# insider.net
KiCad netlist of a schematic drawn in EAGLE
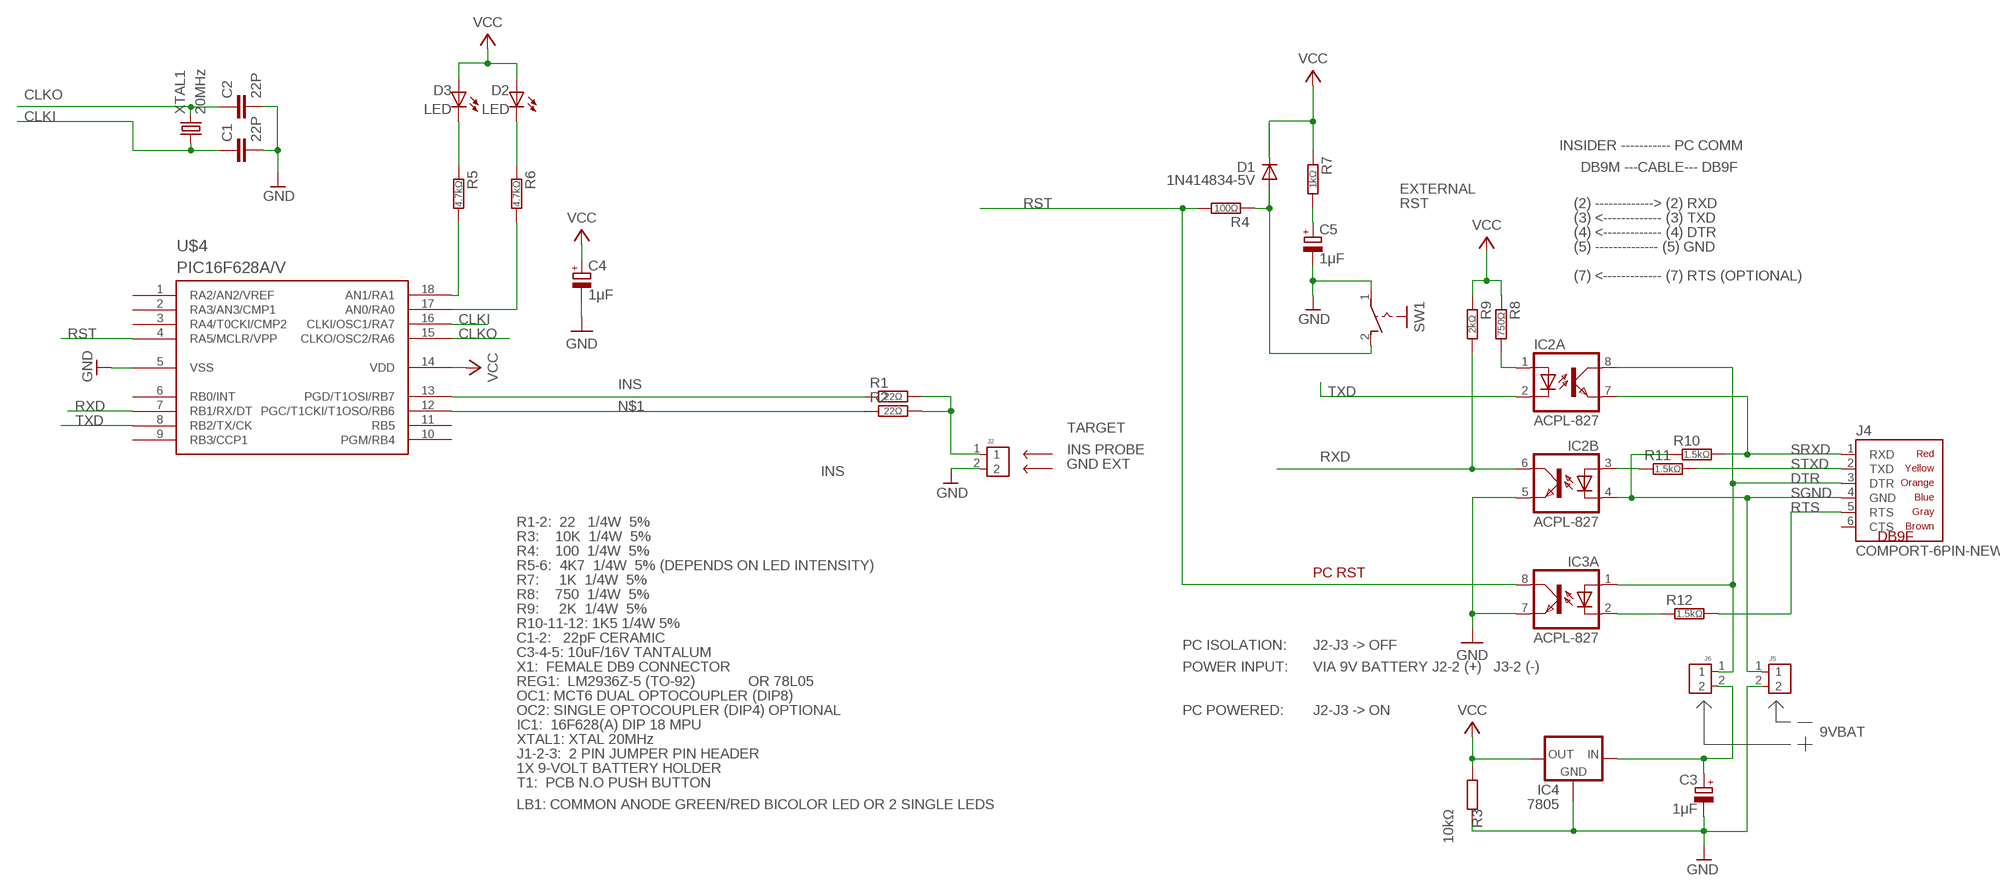
[diagram p0: schematic, sheet 1]

(export (version "E")
  (design (tool "Eeschema 10.0.6"))
  (components
    (comp (ref "C1")
      (value "22P")
      (footprint "eagle-import:C025-020X036")
      (libsource (lib "eagle-import") (part "C025-020X036"))
    )
    (comp (ref "C2")
      (value "22P")
      (footprint "eagle-import:C025-020X036")
      (libsource (lib "eagle-import") (part "C025-020X036"))
    )
    (comp (ref "C3")
      (value "1μF")
      (footprint "eagle-import:E2.5-4_V")
      (libsource (lib "eagle-import") (part "CPOLE2,5-4/V"))
    )
    (comp (ref "C4")
      (value "1μF")
      (footprint "eagle-import:E2.5-4_V")
      (libsource (lib "eagle-import") (part "CPOLE2,5-4/V"))
    )
    (comp (ref "C5")
      (value "1μF")
      (footprint "eagle-import:E2.5-4_V")
      (libsource (lib "eagle-import") (part "CPOLE2,5-4/V"))
    )
    (comp (ref "D1")
      (value "1N414834-5V")
      (footprint "eagle-import:DO34-5V")
      (libsource (lib "eagle-import") (part "1N414834-5V"))
    )
    (comp (ref "D2")
      (value "LED")
      (footprint "eagle-import:LED3MM")
      (libsource (lib "eagle-import") (part "LED"))
    )
    (comp (ref "D3")
      (value "LED")
      (footprint "eagle-import:LED3MM")
      (libsource (lib "eagle-import") (part "LED"))
    )
    (comp (ref "IC2")
      (value "ACPL-827")
      (footprint "eagle-import:DIL08")
      (libsource (lib "eagle-import") (part "ACPL-827"))
    )
    (comp (ref "IC3")
      (value "ACPL-827")
      (footprint "eagle-import:DIL08")
      (libsource (lib "eagle-import") (part "ACPL-827"))
    )
    (comp (ref "IC4")
      (value "7805")
      (footprint "eagle-import:TO220")
      (libsource (lib "eagle-import") (part "LM78"))
    )
    (comp (ref "J2")
      (value "CONN-2P2P/V")
      (footprint "eagle-import:CONN-2P-V")
      (libsource (lib "eagle-import") (part "CONN-2P2P/V"))
    )
    (comp (ref "J4")
      (value "COMPORT-6PIN-NEW")
      (footprint "eagle-import:RS232-6PIN-NEW")
      (libsource (lib "eagle-import") (part "COMPORT-6PIN-NEW"))
    )
    (comp (ref "J5")
      (value "CONN-2P2P/V")
      (footprint "eagle-import:CONN-2P-V")
      (libsource (lib "eagle-import") (part "CONN-2P2P/V"))
    )
    (comp (ref "J6")
      (value "CONN-2P2P/V")
      (footprint "eagle-import:CONN-2P-V")
      (libsource (lib "eagle-import") (part "CONN-2P2P/V"))
    )
    (comp (ref "R1")
      (value "22Ω")
      (footprint "eagle-import:0204_10")
      (libsource (lib "eagle-import") (part "R0204/10"))
    )
    (comp (ref "R2")
      (value "22Ω")
      (footprint "eagle-import:0204_10")
      (libsource (lib "eagle-import") (part "R0204/10"))
    )
    (comp (ref "R3")
      (value "10kΩ")
      (footprint "eagle-import:0204_10")
      (libsource (lib "eagle-import") (part "R0204/10"))
    )
    (comp (ref "R4")
      (value "100Ω")
      (footprint "eagle-import:0204_15")
      (libsource (lib "eagle-import") (part "R0204/15"))
    )
    (comp (ref "R5")
      (value "4.7kΩ")
      (footprint "eagle-import:0204_10")
      (libsource (lib "eagle-import") (part "R0204/10"))
    )
    (comp (ref "R6")
      (value "4.7kΩ")
      (footprint "eagle-import:0204_10")
      (libsource (lib "eagle-import") (part "R0204/10"))
    )
    (comp (ref "R7")
      (value "1kΩ")
      (footprint "eagle-import:0204_10")
      (libsource (lib "eagle-import") (part "R0204/10"))
    )
    (comp (ref "R8")
      (value "750Ω")
      (footprint "eagle-import:0204_12")
      (libsource (lib "eagle-import") (part "R0204/12"))
    )
    (comp (ref "R9")
      (value "2kΩ")
      (footprint "eagle-import:0204_12")
      (libsource (lib "eagle-import") (part "R0204/12"))
    )
    (comp (ref "R10")
      (value "1.5kΩ")
      (footprint "eagle-import:0204_10")
      (libsource (lib "eagle-import") (part "R0204/10"))
    )
    (comp (ref "R11")
      (value "1.5kΩ")
      (footprint "eagle-import:0204_10")
      (libsource (lib "eagle-import") (part "R0204/10"))
    )
    (comp (ref "R12")
      (value "1.5kΩ")
      (footprint "eagle-import:0204_10")
      (libsource (lib "eagle-import") (part "R0204/10"))
    )
    (comp (ref "SW1")
      (value "PB-1P-1T")
      (footprint "eagle-import:PB-1P1T")
      (libsource (lib "eagle-import") (part "PB-1P-1T"))
    )
    (comp (ref "U$4")
      (value "PIC16F628A/V")
      (footprint "eagle-import:DIL18-3_V")
      (libsource (lib "eagle-import") (part "PIC16F628A/V"))
    )
    (comp (ref "XTAL1")
      (value "20MHz")
      (footprint "eagle-import:HC49")
      (libsource (lib "eagle-import") (part "CRYSTALHC49"))
    )
  )
  (nets
    (net (code "1") (name "/CLKI") (class "Default")
      (node (ref "C1") (pin "1") (pinfunction "1_1") (pintype "passive"))
      (node (ref "U$4") (pin "16") (pinfunction "CLKI/OSC1/RA7_16") (pintype "passive"))
      (node (ref "XTAL1") (pin "1") (pinfunction "1_1") (pintype "passive"))
    )
    (net (code "2") (name "/CLKO") (class "Default")
      (node (ref "C2") (pin "1") (pinfunction "1_1") (pintype "passive"))
      (node (ref "U$4") (pin "15") (pinfunction "CLKO/OSC2/RA6_15") (pintype "passive"))
      (node (ref "XTAL1") (pin "2") (pinfunction "2_2") (pintype "passive"))
    )
    (net (code "3") (name "/DTR") (class "Default")
      (node (ref "IC2") (pin "8") (pinfunction "COL_8") (pintype "passive"))
      (node (ref "IC3") (pin "1") (pinfunction "A_1") (pintype "passive"))
      (node (ref "J4") (pin "3") (pinfunction "DTR_3") (pintype "passive"))
      (node (ref "J6") (pin "1") (pinfunction "1_1") (pintype "bidirectional"))
    )
    (net (code "4") (name "/INS") (class "Default")
      (node (ref "R1") (pin "1") (pinfunction "1_1") (pintype "passive"))
      (node (ref "U$4") (pin "13") (pinfunction "PGD/T1OSI/RB7_13") (pintype "passive"))
    )
    (net (code "5") (name "/N$1") (class "Default")
      (node (ref "R2") (pin "1") (pinfunction "1_1") (pintype "passive"))
      (node (ref "U$4") (pin "12") (pinfunction "PGC/T1CKI/T1OSO/RB6_12") (pintype "passive"))
    )
    (net (code "6") (name "/RST") (class "Default")
      (node (ref "IC3") (pin "8") (pinfunction "COL_8") (pintype "passive"))
      (node (ref "R4") (pin "2") (pinfunction "2_2") (pintype "passive"))
      (node (ref "U$4") (pin "4") (pinfunction "RA5/MCLR/VPP_4") (pintype "passive"))
    )
    (net (code "7") (name "/RTS") (class "Default")
      (node (ref "J4") (pin "5") (pinfunction "RTS_5") (pintype "passive"))
      (node (ref "R12") (pin "2") (pinfunction "2_2") (pintype "passive"))
    )
    (net (code "8") (name "/RXD") (class "Default")
      (node (ref "IC2") (pin "6") (pinfunction "COL_6") (pintype "passive"))
      (node (ref "R9") (pin "2") (pinfunction "2_2") (pintype "passive"))
      (node (ref "U$4") (pin "7") (pinfunction "RB1/RX/DT_7") (pintype "passive"))
    )
    (net (code "9") (name "/SGND") (class "Default")
      (node (ref "IC2") (pin "4") (pinfunction "C_4") (pintype "passive"))
      (node (ref "J4") (pin "4") (pinfunction "GND_4") (pintype "passive"))
      (node (ref "J5") (pin "1") (pinfunction "1_1") (pintype "bidirectional"))
      (node (ref "R10") (pin "1") (pinfunction "1_1") (pintype "passive"))
    )
    (net (code "10") (name "/SRXD") (class "Default")
      (node (ref "IC2") (pin "7") (pinfunction "EMIT_7") (pintype "passive"))
      (node (ref "J4") (pin "1") (pinfunction "RXD_1") (pintype "passive"))
      (node (ref "R10") (pin "2") (pinfunction "2_2") (pintype "passive"))
    )
    (net (code "11") (name "/STXD") (class "Default")
      (node (ref "J4") (pin "2") (pinfunction "TXD_2") (pintype "passive"))
      (node (ref "R11") (pin "2") (pinfunction "2_2") (pintype "passive"))
    )
    (net (code "12") (name "/TXD") (class "Default")
      (node (ref "IC2") (pin "2") (pinfunction "C_2") (pintype "passive"))
      (node (ref "U$4") (pin "8") (pinfunction "RB2/TX/CK_8") (pintype "passive"))
    )
    (net (code "13") (name "GND") (class "Default")
      (node (ref "C1") (pin "2") (pinfunction "2_2") (pintype "passive"))
      (node (ref "C2") (pin "2") (pinfunction "2_2") (pintype "passive"))
      (node (ref "C3") (pin "-") (pinfunction "-_-") (pintype "passive"))
      (node (ref "C4") (pin "-") (pinfunction "-_-") (pintype "passive"))
      (node (ref "C5") (pin "-") (pinfunction "-_-") (pintype "passive"))
      (node (ref "IC2") (pin "5") (pinfunction "EMIT_5") (pintype "passive"))
      (node (ref "IC3") (pin "7") (pinfunction "EMIT_7") (pintype "passive"))
      (node (ref "IC4") (pin "2") (pinfunction "GND_2") (pintype "input"))
      (node (ref "J2") (pin "2") (pinfunction "2_2") (pintype "bidirectional"))
      (node (ref "J5") (pin "2") (pinfunction "2_2") (pintype "bidirectional"))
      (node (ref "R3") (pin "2") (pinfunction "2_2") (pintype "passive"))
      (node (ref "SW1") (pin "1") (pinfunction "P_1") (pintype "passive"))
      (node (ref "U$4") (pin "5") (pinfunction "VSS_5") (pintype "passive"))
    )
    (net (code "14") (name "Net-(C5-Pad+)") (class "Default")
      (node (ref "C5") (pin "+") (pinfunction "+_+") (pintype "passive"))
      (node (ref "R7") (pin "2") (pinfunction "2_2") (pintype "passive"))
    )
    (net (code "15") (name "Net-(D2-C)") (class "Default")
      (node (ref "D2") (pin "K") (pinfunction "C_K") (pintype "passive"))
      (node (ref "R6") (pin "1") (pinfunction "1_1") (pintype "passive"))
    )
    (net (code "16") (name "Net-(D3-C)") (class "Default")
      (node (ref "D3") (pin "K") (pinfunction "C_K") (pintype "passive"))
      (node (ref "R5") (pin "1") (pinfunction "1_1") (pintype "passive"))
    )
    (net (code "17") (name "Net-(IC2A-A)") (class "Default")
      (node (ref "IC2") (pin "1") (pinfunction "A_1") (pintype "passive"))
      (node (ref "R8") (pin "2") (pinfunction "2_2") (pintype "passive"))
    )
    (net (code "18") (name "Net-(IC2B-A)") (class "Default")
      (node (ref "IC2") (pin "3") (pinfunction "A_3") (pintype "passive"))
      (node (ref "R11") (pin "1") (pinfunction "1_1") (pintype "passive"))
    )
    (net (code "19") (name "Net-(IC3A-C)") (class "Default")
      (node (ref "IC3") (pin "2") (pinfunction "C_2") (pintype "passive"))
      (node (ref "R12") (pin "1") (pinfunction "1_1") (pintype "passive"))
    )
    (net (code "20") (name "Net-(IC4-IN)") (class "Default")
      (node (ref "C3") (pin "+") (pinfunction "+_+") (pintype "passive"))
      (node (ref "IC4") (pin "1") (pinfunction "IN_1") (pintype "input"))
      (node (ref "J6") (pin "2") (pinfunction "2_2") (pintype "bidirectional"))
    )
    (net (code "21") (name "Net-(J2-Pad1)") (class "Default")
      (node (ref "J2") (pin "1") (pinfunction "1_1") (pintype "bidirectional"))
      (node (ref "R1") (pin "2") (pinfunction "2_2") (pintype "passive"))
      (node (ref "R2") (pin "2") (pinfunction "2_2") (pintype "passive"))
    )
    (net (code "22") (name "Net-(SW1-S)") (class "Default")
      (node (ref "D1") (pin "A") (pinfunction "A_A") (pintype "passive"))
      (node (ref "R4") (pin "1") (pinfunction "1_1") (pintype "passive"))
      (node (ref "SW1") (pin "2") (pinfunction "S_2") (pintype "passive"))
    )
    (net (code "23") (name "Net-(U$4-AN0{slash}RA0)") (class "Default")
      (node (ref "R6") (pin "2") (pinfunction "2_2") (pintype "passive"))
      (node (ref "U$4") (pin "17") (pinfunction "AN0/RA0_17") (pintype "passive"))
    )
    (net (code "24") (name "Net-(U$4-AN1{slash}RA1)") (class "Default")
      (node (ref "R5") (pin "2") (pinfunction "2_2") (pintype "passive"))
      (node (ref "U$4") (pin "18") (pinfunction "AN1/RA1_18") (pintype "passive"))
    )
    (net (code "25") (name "VCC") (class "Default")
      (node (ref "C4") (pin "+") (pinfunction "+_+") (pintype "passive"))
      (node (ref "D1") (pin "C") (pinfunction "C_C") (pintype "passive"))
      (node (ref "D2") (pin "A") (pinfunction "A_A") (pintype "passive"))
      (node (ref "D3") (pin "A") (pinfunction "A_A") (pintype "passive"))
      (node (ref "IC4") (pin "3") (pinfunction "OUT_3") (pintype "output"))
      (node (ref "R3") (pin "1") (pinfunction "1_1") (pintype "passive"))
      (node (ref "R7") (pin "1") (pinfunction "1_1") (pintype "passive"))
      (node (ref "R8") (pin "1") (pinfunction "1_1") (pintype "passive"))
      (node (ref "R9") (pin "1") (pinfunction "1_1") (pintype "passive"))
      (node (ref "U$4") (pin "14") (pinfunction "VDD_14") (pintype "passive"))
    )
    (net (code "26") (name "unconnected-(J4-CTS-Pad6)") (class "Default")
      (node (ref "J4") (pin "6") (pinfunction "CTS_6") (pintype "passive"))
    )
    (net (code "27") (name "unconnected-(U$4-PGM{slash}RB4-Pad10)") (class "Default")
      (node (ref "U$4") (pin "10") (pinfunction "PGM/RB4_10") (pintype "passive"))
    )
    (net (code "28") (name "unconnected-(U$4-RA2{slash}AN2{slash}VREF-Pad1)") (class "Default")
      (node (ref "U$4") (pin "1") (pinfunction "RA2/AN2/VREF_1") (pintype "passive"))
    )
    (net (code "29") (name "unconnected-(U$4-RA3{slash}AN3{slash}CMP1-Pad2)") (class "Default")
      (node (ref "U$4") (pin "2") (pinfunction "RA3/AN3/CMP1_2") (pintype "passive"))
    )
    (net (code "30") (name "unconnected-(U$4-RA4{slash}T0CKI{slash}CMP2-Pad3)") (class "Default")
      (node (ref "U$4") (pin "3") (pinfunction "RA4/T0CKI/CMP2_3") (pintype "passive"))
    )
    (net (code "31") (name "unconnected-(U$4-RB0{slash}INT-Pad6)") (class "Default")
      (node (ref "U$4") (pin "6") (pinfunction "RB0/INT_6") (pintype "passive"))
    )
    (net (code "32") (name "unconnected-(U$4-RB3{slash}CCP1-Pad9)") (class "Default")
      (node (ref "U$4") (pin "9") (pinfunction "RB3/CCP1_9") (pintype "passive"))
    )
    (net (code "33") (name "unconnected-(U$4-RB5-Pad11)") (class "Default")
      (node (ref "U$4") (pin "11") (pinfunction "RB5_11") (pintype "passive"))
    )
  )
)
